# rc2014_6502.net
KiCad netlist of a schematic drawn in EAGLE
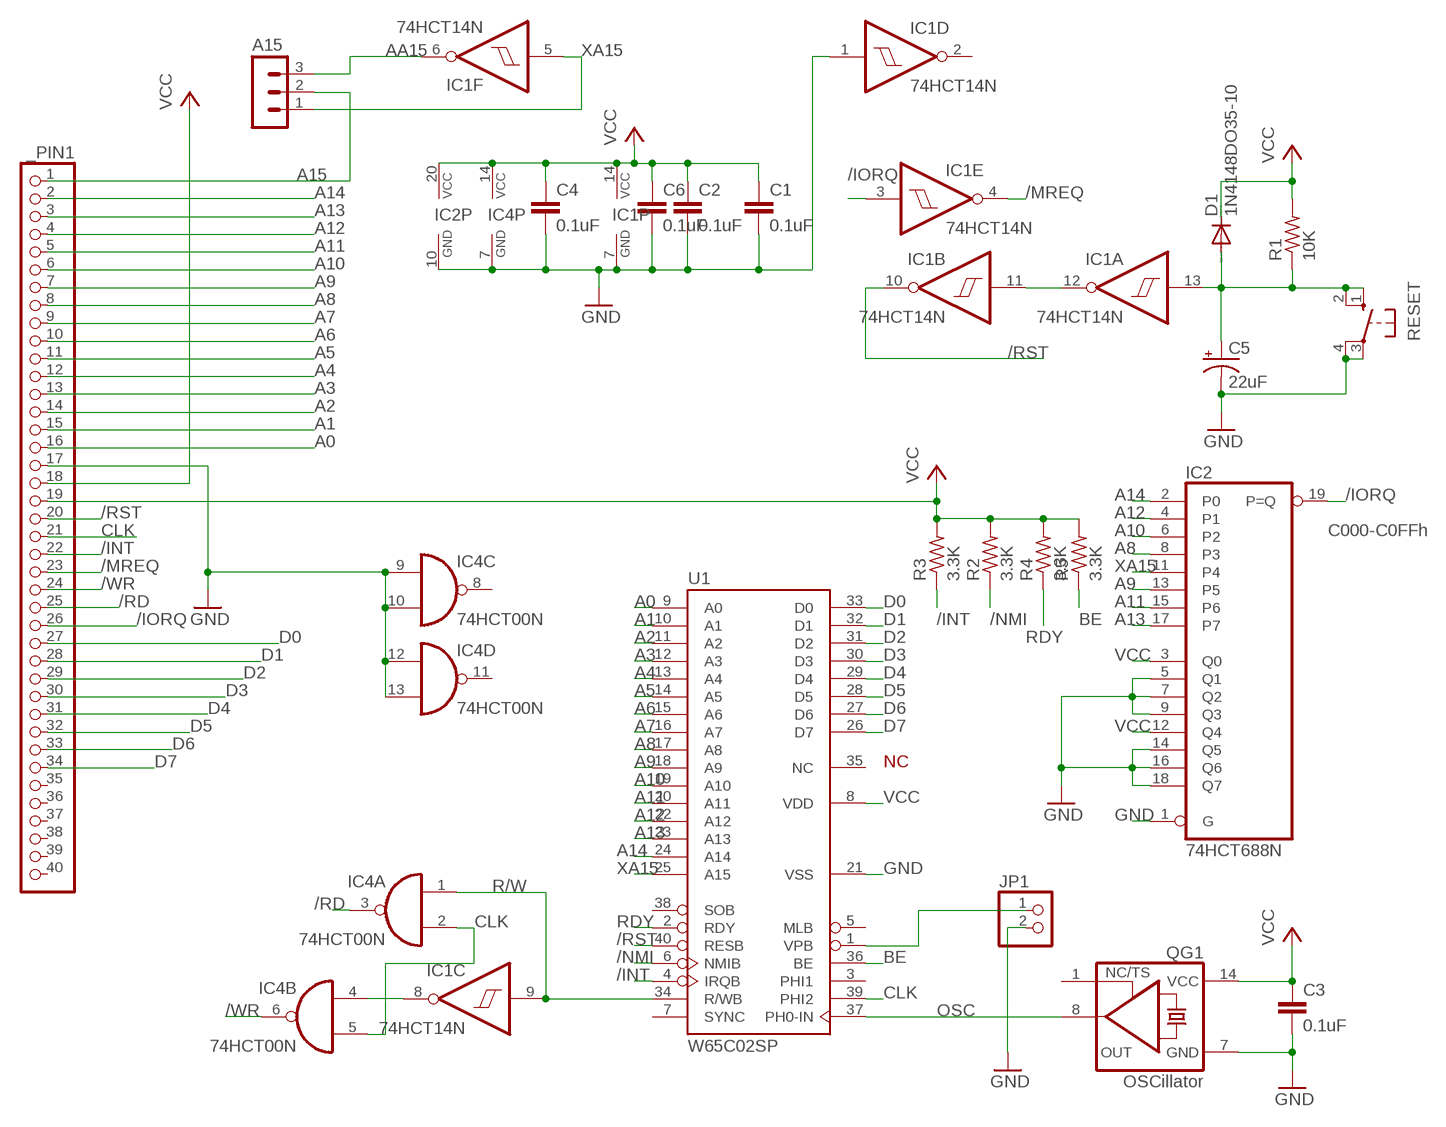
[diagram p0: schematic, sheet 1]

(export (version "E")
  (design (tool "Eeschema 10.0.6"))
  (components
    (comp (ref "A15")
      (value "MA03-1")
      (footprint "eagle-import:MA03-1")
      (libsource (lib "eagle-import") (part "MA03-1"))
    )
    (comp (ref "C1")
      (value "0.1uF")
      (footprint "eagle-import:C050-024X044")
      (libsource (lib "eagle-import") (part "C-EU050-024X044"))
    )
    (comp (ref "C2")
      (value "0.1uF")
      (footprint "eagle-import:C050-024X044")
      (libsource (lib "eagle-import") (part "C-EU050-024X044"))
    )
    (comp (ref "C3")
      (value "0.1uF")
      (footprint "eagle-import:C050-024X044")
      (libsource (lib "eagle-import") (part "C-EU050-024X044"))
    )
    (comp (ref "C4")
      (value "0.1uF")
      (footprint "eagle-import:C050-024X044")
      (libsource (lib "eagle-import") (part "C-EU050-024X044"))
    )
    (comp (ref "C5")
      (value "22uF")
      (footprint "eagle-import:TAP5-80")
      (libsource (lib "eagle-import") (part "CPOL-USTAP5-80"))
    )
    (comp (ref "C6")
      (value "0.1uF")
      (footprint "eagle-import:C050-024X044")
      (libsource (lib "eagle-import") (part "C-EU050-024X044"))
    )
    (comp (ref "D1")
      (value "1N4148DO35-10")
      (footprint "eagle-import:DO35-10")
      (libsource (lib "eagle-import") (part "1N4148DO35-10"))
    )
    (comp (ref "IC1")
      (value "74HCT14N")
      (footprint "eagle-import:DIL14")
      (libsource (lib "eagle-import") (part "7414NHCT"))
    )
    (comp (ref "IC2")
      (value "74HCT688N")
      (footprint "eagle-import:DIL20")
      (libsource (lib "eagle-import") (part "74688NHCT"))
    )
    (comp (ref "IC4")
      (value "74HCT00N")
      (footprint "eagle-import:DIL14")
      (libsource (lib "eagle-import") (part "7400NHCT"))
    )
    (comp (ref "JP1")
      (value "PINHD-1X2")
      (footprint "eagle-import:1X02")
      (libsource (lib "eagle-import") (part "PINHD-1X2"))
    )
    (comp (ref "QG1")
      (value "OSCillator")
      (footprint "eagle-import:DIL14S")
      (libsource (lib "eagle-import") (part "XO-14"))
    )
    (comp (ref "R1")
      (value "10K")
      (footprint "eagle-import:0207_10")
      (libsource (lib "eagle-import") (part "R-US_0207/10"))
    )
    (comp (ref "R2")
      (value "3.3K")
      (footprint "eagle-import:0207_10")
      (libsource (lib "eagle-import") (part "R-US_0207/10"))
    )
    (comp (ref "R3")
      (value "3.3K")
      (footprint "eagle-import:0207_10")
      (libsource (lib "eagle-import") (part "R-US_0207/10"))
    )
    (comp (ref "R4")
      (value "3.3K")
      (footprint "eagle-import:0207_10")
      (libsource (lib "eagle-import") (part "R-US_0207/10"))
    )
    (comp (ref "R5")
      (value "3.3K")
      (footprint "eagle-import:0207_10")
      (libsource (lib "eagle-import") (part "R-US_0207/10"))
    )
    (comp (ref "RESET")
      (value "10-XX")
      (footprint "eagle-import:B3F-10XX")
      (fields (field (name "MPN") "B3F-1000"))
      (libsource (lib "eagle-import") (part "10-XX"))
    )
    (comp (ref "U1")
      (value "W65C02SP")
      (footprint "eagle-import:DIP-40")
      (libsource (lib "eagle-import") (part "W65C02SP"))
    )
    (comp (ref "_PIN1")
      (value "PINHD-1X40")
      (footprint "eagle-import:1X40")
      (libsource (lib "eagle-import") (part "PINHD-1X40"))
    )
  )
  (nets
    (net (code "1") (name "/A0") (class "Default")
      (node (ref "U1") (pin "9") (pinfunction "A0_9") (pintype "bidirectional"))
      (node (ref "_PIN1") (pin "16") (pinfunction "16_16") (pintype "passive"))
    )
    (net (code "2") (name "/A1") (class "Default")
      (node (ref "U1") (pin "10") (pinfunction "A1_10") (pintype "bidirectional"))
      (node (ref "_PIN1") (pin "15") (pinfunction "15_15") (pintype "passive"))
    )
    (net (code "3") (name "/A2") (class "Default")
      (node (ref "U1") (pin "11") (pinfunction "A2_11") (pintype "bidirectional"))
      (node (ref "_PIN1") (pin "14") (pinfunction "14_14") (pintype "passive"))
    )
    (net (code "4") (name "/A3") (class "Default")
      (node (ref "U1") (pin "12") (pinfunction "A3_12") (pintype "bidirectional"))
      (node (ref "_PIN1") (pin "13") (pinfunction "13_13") (pintype "passive"))
    )
    (net (code "5") (name "/A4") (class "Default")
      (node (ref "U1") (pin "13") (pinfunction "A4_13") (pintype "bidirectional"))
      (node (ref "_PIN1") (pin "12") (pinfunction "12_12") (pintype "passive"))
    )
    (net (code "6") (name "/A5") (class "Default")
      (node (ref "U1") (pin "14") (pinfunction "A5_14") (pintype "bidirectional"))
      (node (ref "_PIN1") (pin "11") (pinfunction "11_11") (pintype "passive"))
    )
    (net (code "7") (name "/A6") (class "Default")
      (node (ref "U1") (pin "15") (pinfunction "A6_15") (pintype "bidirectional"))
      (node (ref "_PIN1") (pin "10") (pinfunction "10_10") (pintype "passive"))
    )
    (net (code "8") (name "/A7") (class "Default")
      (node (ref "U1") (pin "16") (pinfunction "A7_16") (pintype "bidirectional"))
      (node (ref "_PIN1") (pin "9") (pinfunction "9_9") (pintype "passive"))
    )
    (net (code "9") (name "/A8") (class "Default")
      (node (ref "IC2") (pin "8") (pinfunction "P3_8") (pintype "input"))
      (node (ref "U1") (pin "17") (pinfunction "A8_17") (pintype "bidirectional"))
      (node (ref "_PIN1") (pin "8") (pinfunction "8_8") (pintype "passive"))
    )
    (net (code "10") (name "/A9") (class "Default")
      (node (ref "IC2") (pin "13") (pinfunction "P5_13") (pintype "input"))
      (node (ref "U1") (pin "18") (pinfunction "A9_18") (pintype "bidirectional"))
      (node (ref "_PIN1") (pin "7") (pinfunction "7_7") (pintype "passive"))
    )
    (net (code "11") (name "/A10") (class "Default")
      (node (ref "IC2") (pin "6") (pinfunction "P2_6") (pintype "input"))
      (node (ref "U1") (pin "19") (pinfunction "A10_19") (pintype "bidirectional"))
      (node (ref "_PIN1") (pin "6") (pinfunction "6_6") (pintype "passive"))
    )
    (net (code "12") (name "/A11") (class "Default")
      (node (ref "IC2") (pin "15") (pinfunction "P6_15") (pintype "input"))
      (node (ref "U1") (pin "20") (pinfunction "A11_20") (pintype "bidirectional"))
      (node (ref "_PIN1") (pin "5") (pinfunction "5_5") (pintype "passive"))
    )
    (net (code "13") (name "/A12") (class "Default")
      (node (ref "IC2") (pin "4") (pinfunction "P1_4") (pintype "input"))
      (node (ref "U1") (pin "22") (pinfunction "A12_22") (pintype "bidirectional"))
      (node (ref "_PIN1") (pin "4") (pinfunction "4_4") (pintype "passive"))
    )
    (net (code "14") (name "/A13") (class "Default")
      (node (ref "IC2") (pin "17") (pinfunction "P7_17") (pintype "input"))
      (node (ref "U1") (pin "23") (pinfunction "A13_23") (pintype "bidirectional"))
      (node (ref "_PIN1") (pin "3") (pinfunction "3_3") (pintype "passive"))
    )
    (net (code "15") (name "/A14") (class "Default")
      (node (ref "IC2") (pin "2") (pinfunction "P0_2") (pintype "input"))
      (node (ref "U1") (pin "24") (pinfunction "A14_24") (pintype "bidirectional"))
      (node (ref "_PIN1") (pin "2") (pinfunction "2_2") (pintype "passive"))
    )
    (net (code "16") (name "/A15") (class "Default")
      (node (ref "A15") (pin "2") (pinfunction "2_2") (pintype "passive"))
      (node (ref "_PIN1") (pin "1") (pinfunction "1_1") (pintype "passive"))
    )
    (net (code "17") (name "/AA15") (class "Default")
      (node (ref "A15") (pin "3") (pinfunction "3_3") (pintype "passive"))
      (node (ref "IC1") (pin "6") (pinfunction "O_6") (pintype "output"))
    )
    (net (code "18") (name "/BE") (class "Default")
      (node (ref "R5") (pin "1") (pinfunction "1_1") (pintype "passive"))
      (node (ref "U1") (pin "36") (pinfunction "BE_36") (pintype "input"))
    )
    (net (code "19") (name "/CLK") (class "Default")
      (node (ref "IC4") (pin "2") (pinfunction "I1_2") (pintype "input"))
      (node (ref "IC4") (pin "5") (pinfunction "I1_5") (pintype "input"))
      (node (ref "U1") (pin "39") (pinfunction "PHI2_39") (pintype "output"))
      (node (ref "_PIN1") (pin "21") (pinfunction "21_21") (pintype "passive"))
    )
    (net (code "20") (name "/D0") (class "Default")
      (node (ref "U1") (pin "33") (pinfunction "D0_33") (pintype "bidirectional"))
      (node (ref "_PIN1") (pin "27") (pinfunction "27_27") (pintype "passive"))
    )
    (net (code "21") (name "/D1") (class "Default")
      (node (ref "U1") (pin "32") (pinfunction "D1_32") (pintype "bidirectional"))
      (node (ref "_PIN1") (pin "28") (pinfunction "28_28") (pintype "passive"))
    )
    (net (code "22") (name "/D2") (class "Default")
      (node (ref "U1") (pin "31") (pinfunction "D2_31") (pintype "bidirectional"))
      (node (ref "_PIN1") (pin "29") (pinfunction "29_29") (pintype "passive"))
    )
    (net (code "23") (name "/D3") (class "Default")
      (node (ref "U1") (pin "30") (pinfunction "D3_30") (pintype "bidirectional"))
      (node (ref "_PIN1") (pin "30") (pinfunction "30_30") (pintype "passive"))
    )
    (net (code "24") (name "/D4") (class "Default")
      (node (ref "U1") (pin "29") (pinfunction "D4_29") (pintype "bidirectional"))
      (node (ref "_PIN1") (pin "31") (pinfunction "31_31") (pintype "passive"))
    )
    (net (code "25") (name "/D5") (class "Default")
      (node (ref "U1") (pin "28") (pinfunction "D5_28") (pintype "bidirectional"))
      (node (ref "_PIN1") (pin "32") (pinfunction "32_32") (pintype "passive"))
    )
    (net (code "26") (name "/D6") (class "Default")
      (node (ref "U1") (pin "27") (pinfunction "D6_27") (pintype "bidirectional"))
      (node (ref "_PIN1") (pin "33") (pinfunction "33_33") (pintype "passive"))
    )
    (net (code "27") (name "/D7") (class "Default")
      (node (ref "U1") (pin "26") (pinfunction "D7_26") (pintype "bidirectional"))
      (node (ref "_PIN1") (pin "34") (pinfunction "34_34") (pintype "passive"))
    )
    (net (code "28") (name "/OSC") (class "Default")
      (node (ref "QG1") (pin "8") (pinfunction "OUT_8") (pintype "output"))
      (node (ref "U1") (pin "37") (pinfunction "PH0-IN_37") (pintype "input"))
    )
    (net (code "29") (name "/RDY") (class "Default")
      (node (ref "R4") (pin "1") (pinfunction "1_1") (pintype "passive"))
      (node (ref "U1") (pin "2") (pinfunction "RDY_2") (pintype "bidirectional"))
    )
    (net (code "30") (name "/R{slash}W") (class "Default")
      (node (ref "IC1") (pin "9") (pinfunction "I_9") (pintype "input"))
      (node (ref "IC4") (pin "1") (pinfunction "I0_1") (pintype "input"))
      (node (ref "U1") (pin "34") (pinfunction "R/WB_34") (pintype "output"))
    )
    (net (code "31") (name "/XA15") (class "Default")
      (node (ref "A15") (pin "1") (pinfunction "1_1") (pintype "passive"))
      (node (ref "IC1") (pin "5") (pinfunction "I_5") (pintype "input"))
      (node (ref "IC2") (pin "11") (pinfunction "P4_11") (pintype "input"))
      (node (ref "U1") (pin "25") (pinfunction "A15_25") (pintype "bidirectional"))
    )
    (net (code "32") (name "/{slash}INT") (class "Default")
      (node (ref "R3") (pin "1") (pinfunction "1_1") (pintype "passive"))
      (node (ref "U1") (pin "4") (pinfunction "IRQB_4") (pintype "input"))
      (node (ref "_PIN1") (pin "22") (pinfunction "22_22") (pintype "passive"))
    )
    (net (code "33") (name "/{slash}IORQ") (class "Default")
      (node (ref "IC1") (pin "3") (pinfunction "I_3") (pintype "input"))
      (node (ref "IC2") (pin "19") (pinfunction "P=Q_19") (pintype "output"))
      (node (ref "_PIN1") (pin "26") (pinfunction "26_26") (pintype "passive"))
    )
    (net (code "34") (name "/{slash}MREQ") (class "Default")
      (node (ref "IC1") (pin "4") (pinfunction "O_4") (pintype "output"))
      (node (ref "_PIN1") (pin "23") (pinfunction "23_23") (pintype "passive"))
    )
    (net (code "35") (name "/{slash}NMI") (class "Default")
      (node (ref "R2") (pin "1") (pinfunction "1_1") (pintype "passive"))
      (node (ref "U1") (pin "6") (pinfunction "NMIB_6") (pintype "input"))
    )
    (net (code "36") (name "/{slash}RD") (class "Default")
      (node (ref "IC4") (pin "3") (pinfunction "O_3") (pintype "output"))
      (node (ref "_PIN1") (pin "25") (pinfunction "25_25") (pintype "passive"))
    )
    (net (code "37") (name "/{slash}RST") (class "Default")
      (node (ref "IC1") (pin "10") (pinfunction "O_10") (pintype "output"))
      (node (ref "U1") (pin "40") (pinfunction "RESB_40") (pintype "input"))
      (node (ref "_PIN1") (pin "20") (pinfunction "20_20") (pintype "passive"))
    )
    (net (code "38") (name "/{slash}WR") (class "Default")
      (node (ref "IC4") (pin "6") (pinfunction "O_6") (pintype "output"))
      (node (ref "_PIN1") (pin "24") (pinfunction "24_24") (pintype "passive"))
    )
    (net (code "39") (name "GND") (class "Default")
      (node (ref "C1") (pin "2") (pinfunction "2_2") (pintype "passive"))
      (node (ref "C2") (pin "2") (pinfunction "2_2") (pintype "passive"))
      (node (ref "C3") (pin "2") (pinfunction "2_2") (pintype "passive"))
      (node (ref "C4") (pin "2") (pinfunction "2_2") (pintype "passive"))
      (node (ref "C5") (pin "-") (pinfunction "-_-") (pintype "passive"))
      (node (ref "C6") (pin "2") (pinfunction "2_2") (pintype "passive"))
      (node (ref "IC1") (pin "1") (pinfunction "I_1") (pintype "input"))
      (node (ref "IC1") (pin "7") (pinfunction "GND_7") (pintype "power_in"))
      (node (ref "IC2") (pin "1") (pinfunction "G_1") (pintype "input"))
      (node (ref "IC2") (pin "10") (pinfunction "GND_10") (pintype "power_in"))
      (node (ref "IC2") (pin "14") (pinfunction "Q5_14") (pintype "input"))
      (node (ref "IC2") (pin "16") (pinfunction "Q6_16") (pintype "input"))
      (node (ref "IC2") (pin "18") (pinfunction "Q7_18") (pintype "input"))
      (node (ref "IC2") (pin "5") (pinfunction "Q1_5") (pintype "input"))
      (node (ref "IC2") (pin "7") (pinfunction "Q2_7") (pintype "input"))
      (node (ref "IC2") (pin "9") (pinfunction "Q3_9") (pintype "input"))
      (node (ref "IC4") (pin "10") (pinfunction "I1_10") (pintype "input"))
      (node (ref "IC4") (pin "12") (pinfunction "I0_12") (pintype "input"))
      (node (ref "IC4") (pin "13") (pinfunction "I1_13") (pintype "input"))
      (node (ref "IC4") (pin "7") (pinfunction "GND_7") (pintype "power_in"))
      (node (ref "IC4") (pin "9") (pinfunction "I0_9") (pintype "input"))
      (node (ref "JP1") (pin "2") (pinfunction "2_2") (pintype "passive"))
      (node (ref "QG1") (pin "7") (pinfunction "GND_7") (pintype "power_in"))
      (node (ref "RESET") (pin "3") (pinfunction "P_3") (pintype "passive"))
      (node (ref "RESET") (pin "4") (pinfunction "P1_4") (pintype "passive"))
      (node (ref "U1") (pin "21") (pinfunction "VSS_21") (pintype "power_in"))
      (node (ref "_PIN1") (pin "17") (pinfunction "17_17") (pintype "passive"))
    )
    (net (code "40") (name "Net-(IC1A-I)") (class "Default")
      (node (ref "C5") (pin "+") (pinfunction "+_+") (pintype "passive"))
      (node (ref "D1") (pin "A") (pinfunction "A_A") (pintype "passive"))
      (node (ref "IC1") (pin "13") (pinfunction "I_13") (pintype "input"))
      (node (ref "R1") (pin "1") (pinfunction "1_1") (pintype "passive"))
      (node (ref "RESET") (pin "1") (pinfunction "S_1") (pintype "passive"))
      (node (ref "RESET") (pin "2") (pinfunction "S1_2") (pintype "passive"))
    )
    (net (code "41") (name "Net-(IC1A-O)") (class "Default")
      (node (ref "IC1") (pin "11") (pinfunction "I_11") (pintype "input"))
      (node (ref "IC1") (pin "12") (pinfunction "O_12") (pintype "output"))
    )
    (net (code "42") (name "Net-(IC1C-O)") (class "Default")
      (node (ref "IC1") (pin "8") (pinfunction "O_8") (pintype "output"))
      (node (ref "IC4") (pin "4") (pinfunction "I0_4") (pintype "input"))
    )
    (net (code "43") (name "Net-(U1-VPB)") (class "Default")
      (node (ref "JP1") (pin "1") (pinfunction "1_1") (pintype "passive"))
      (node (ref "U1") (pin "1") (pinfunction "VPB_1") (pintype "output"))
    )
    (net (code "44") (name "VCC") (class "Default")
      (node (ref "C1") (pin "1") (pinfunction "1_1") (pintype "passive"))
      (node (ref "C2") (pin "1") (pinfunction "1_1") (pintype "passive"))
      (node (ref "C3") (pin "1") (pinfunction "1_1") (pintype "passive"))
      (node (ref "C4") (pin "1") (pinfunction "1_1") (pintype "passive"))
      (node (ref "C6") (pin "1") (pinfunction "1_1") (pintype "passive"))
      (node (ref "D1") (pin "C") (pinfunction "C_C") (pintype "passive"))
      (node (ref "IC1") (pin "14") (pinfunction "VCC_14") (pintype "power_in"))
      (node (ref "IC2") (pin "12") (pinfunction "Q4_12") (pintype "input"))
      (node (ref "IC2") (pin "20") (pinfunction "VCC_20") (pintype "power_in"))
      (node (ref "IC2") (pin "3") (pinfunction "Q0_3") (pintype "input"))
      (node (ref "IC4") (pin "14") (pinfunction "VCC_14") (pintype "power_in"))
      (node (ref "QG1") (pin "14") (pinfunction "VCC_14") (pintype "power_in"))
      (node (ref "R1") (pin "2") (pinfunction "2_2") (pintype "passive"))
      (node (ref "R2") (pin "2") (pinfunction "2_2") (pintype "passive"))
      (node (ref "R3") (pin "2") (pinfunction "2_2") (pintype "passive"))
      (node (ref "R4") (pin "2") (pinfunction "2_2") (pintype "passive"))
      (node (ref "R5") (pin "2") (pinfunction "2_2") (pintype "passive"))
      (node (ref "U1") (pin "8") (pinfunction "VDD_8") (pintype "power_in"))
      (node (ref "_PIN1") (pin "18") (pinfunction "18_18") (pintype "passive"))
      (node (ref "_PIN1") (pin "19") (pinfunction "19_19") (pintype "passive"))
    )
    (net (code "45") (name "unconnected-(IC1D-O-Pad2)") (class "Default")
      (node (ref "IC1") (pin "2") (pinfunction "O_2") (pintype "output"))
    )
    (net (code "46") (name "unconnected-(IC4C-O-Pad8)") (class "Default")
      (node (ref "IC4") (pin "8") (pinfunction "O_8") (pintype "output"))
    )
    (net (code "47") (name "unconnected-(IC4D-O-Pad11)") (class "Default")
      (node (ref "IC4") (pin "11") (pinfunction "O_11") (pintype "output"))
    )
    (net (code "48") (name "unconnected-(QG1-TS-Pad1)") (class "Default")
      (node (ref "QG1") (pin "1") (pinfunction "TS_1") (pintype "passive"))
    )
    (net (code "49") (name "unconnected-(U1-MLB-Pad5)") (class "Default")
      (node (ref "U1") (pin "5") (pinfunction "MLB_5") (pintype "output"))
    )
    (net (code "50") (name "unconnected-(U1-NC-Pad35)") (class "Default")
      (node (ref "U1") (pin "35") (pinfunction "NC_35") (pintype "no_connect"))
    )
    (net (code "51") (name "unconnected-(U1-PHI1-Pad3)") (class "Default")
      (node (ref "U1") (pin "3") (pinfunction "PHI1_3") (pintype "output"))
    )
    (net (code "52") (name "unconnected-(U1-SOB-Pad38)") (class "Default")
      (node (ref "U1") (pin "38") (pinfunction "SOB_38") (pintype "input"))
    )
    (net (code "53") (name "unconnected-(U1-SYNC-Pad7)") (class "Default")
      (node (ref "U1") (pin "7") (pinfunction "SYNC_7") (pintype "output"))
    )
    (net (code "54") (name "unconnected-(_PIN1-Pad35)") (class "Default")
      (node (ref "_PIN1") (pin "35") (pinfunction "35_35") (pintype "passive"))
    )
    (net (code "55") (name "unconnected-(_PIN1-Pad36)") (class "Default")
      (node (ref "_PIN1") (pin "36") (pinfunction "36_36") (pintype "passive"))
    )
    (net (code "56") (name "unconnected-(_PIN1-Pad37)") (class "Default")
      (node (ref "_PIN1") (pin "37") (pinfunction "37_37") (pintype "passive"))
    )
    (net (code "57") (name "unconnected-(_PIN1-Pad38)") (class "Default")
      (node (ref "_PIN1") (pin "38") (pinfunction "38_38") (pintype "passive"))
    )
    (net (code "58") (name "unconnected-(_PIN1-Pad39)") (class "Default")
      (node (ref "_PIN1") (pin "39") (pinfunction "39_39") (pintype "passive"))
    )
    (net (code "59") (name "unconnected-(_PIN1-Pad40)") (class "Default")
      (node (ref "_PIN1") (pin "40") (pinfunction "40_40") (pintype "passive"))
    )
  )
)
